# ramanSpectrometer_imagingBoard_CCD.net
KiCad netlist of a schematic drawn in EAGLE
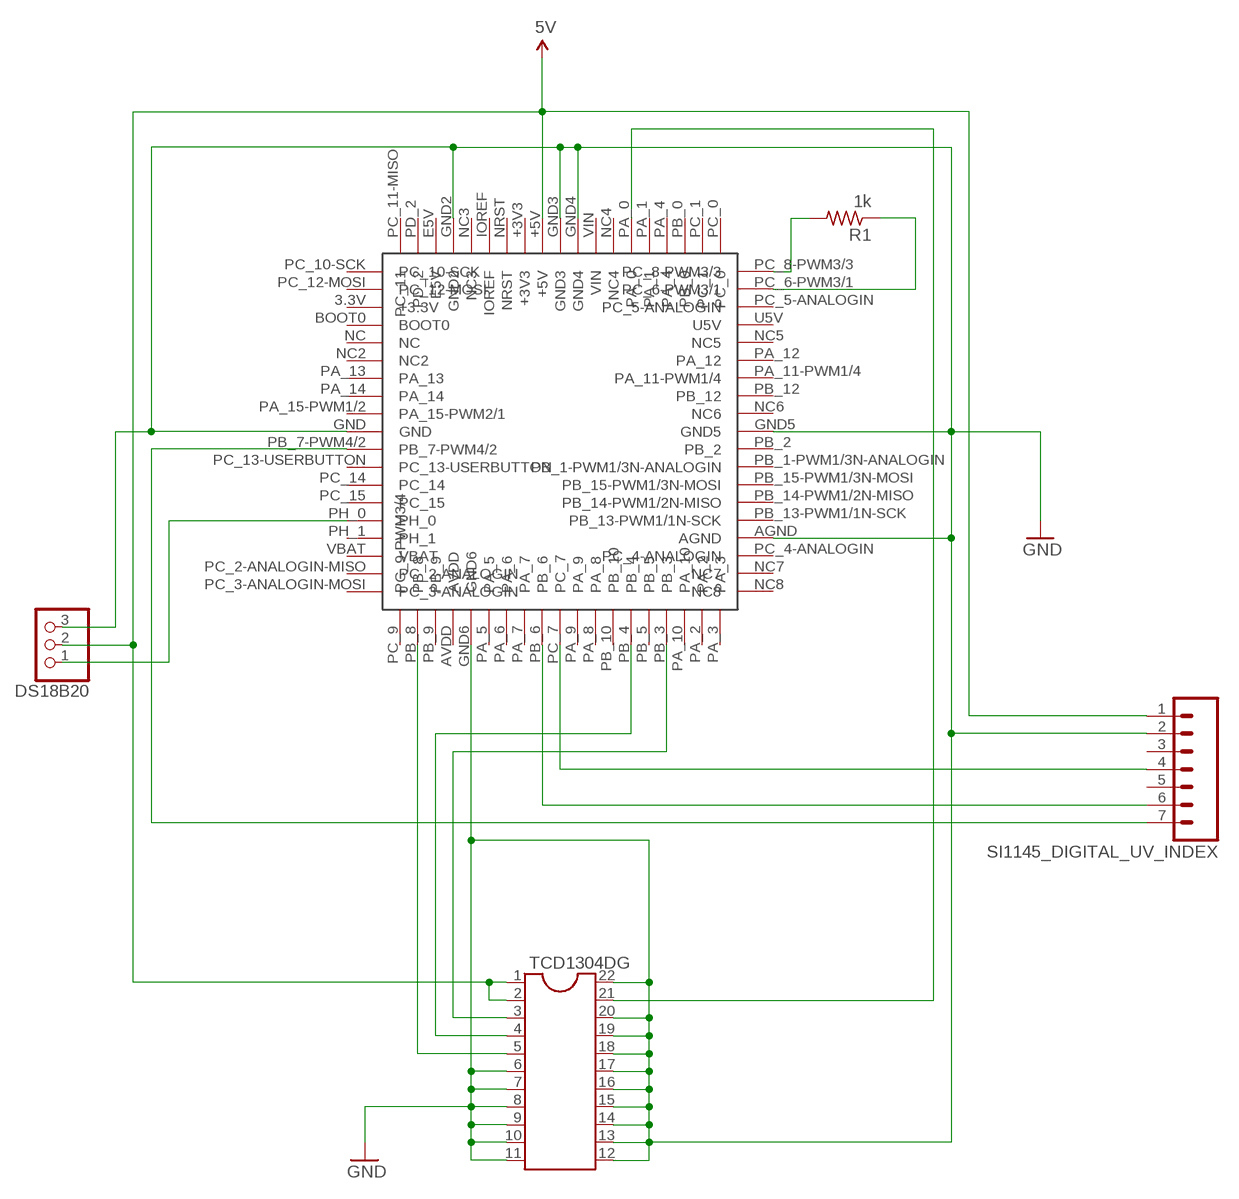
[diagram p0: schematic, sheet 1]

(export (version "E")
  (design (tool "Eeschema 10.0.6"))
  (components
    (comp (ref "DS18B20")
      (value "PINHD-1X3")
      (footprint "eagle-import:1X03")
      (libsource (lib "eagle-import") (part "PINHD-1X3"))
    )
    (comp (ref "R1")
      (value "1k")
      (footprint "eagle-import:M1206")
      (libsource (lib "eagle-import") (part "R-US_M1206"))
    )
    (comp (ref "SI1145_DIGITAL_UV_INDEX")
      (value "M07LOCK")
      (footprint "eagle-import:1X07_LOCK")
      (libsource (lib "eagle-import") (part "M07LOCK"))
    )
    (comp (ref "TCD1304DG")
      (value "DIL22-4")
      (footprint "eagle-import:DIL22-4")
      (libsource (lib "eagle-import") (part "DIL22-4"))
    )
    (comp (ref "U$1")
      (value "STNUCLEOF401RE")
      (footprint "eagle-import:F401-RE")
      (libsource (lib "eagle-import") (part "STNUCLEOF401RE"))
    )
  )
  (nets
    (net (code "1") (name "/+3.3V") (class "Default")
      (node (ref "U$1") (pin "3.3V") (pinfunction "+3.3V_3.3V") (pintype "power_in"))
    )
    (net (code "2") (name "/AVDD") (class "Default")
      (node (ref "U$1") (pin "AVDD") (pinfunction "AVDD_AVDD") (pintype "power_in"))
    )
    (net (code "3") (name "/E5V") (class "Default")
      (node (ref "U$1") (pin "E5V") (pinfunction "E5V_E5V") (pintype "power_in"))
    )
    (net (code "4") (name "/NC6") (class "Default")
      (node (ref "U$1") (pin "NC6") (pinfunction "NC6_NC6") (pintype "power_in"))
    )
    (net (code "5") (name "/VBAT") (class "Default")
      (node (ref "U$1") (pin "VBAT") (pinfunction "VBAT_VBAT") (pintype "power_in"))
    )
    (net (code "6") (name "5V") (class "Default")
      (node (ref "DS18B20") (pin "2") (pinfunction "2_2") (pintype "passive"))
      (node (ref "SI1145_DIGITAL_UV_INDEX") (pin "1") (pinfunction "1_1") (pintype "passive"))
      (node (ref "TCD1304DG") (pin "1") (pinfunction "1_1") (pintype "passive"))
      (node (ref "TCD1304DG") (pin "2") (pinfunction "2_2") (pintype "passive"))
      (node (ref "U$1") (pin "+5V") (pinfunction "+5V_+5V") (pintype "bidirectional"))
    )
    (net (code "7") (name "GND") (class "Default")
      (node (ref "DS18B20") (pin "3") (pinfunction "3_3") (pintype "passive"))
      (node (ref "SI1145_DIGITAL_UV_INDEX") (pin "2") (pinfunction "2_2") (pintype "passive"))
      (node (ref "TCD1304DG") (pin "10") (pinfunction "10_10") (pintype "passive"))
      (node (ref "TCD1304DG") (pin "11") (pinfunction "11_11") (pintype "passive"))
      (node (ref "TCD1304DG") (pin "12") (pinfunction "12_12") (pintype "passive"))
      (node (ref "TCD1304DG") (pin "13") (pinfunction "13_13") (pintype "passive"))
      (node (ref "TCD1304DG") (pin "14") (pinfunction "14_14") (pintype "passive"))
      (node (ref "TCD1304DG") (pin "15") (pinfunction "15_15") (pintype "passive"))
      (node (ref "TCD1304DG") (pin "16") (pinfunction "16_16") (pintype "passive"))
      (node (ref "TCD1304DG") (pin "17") (pinfunction "17_17") (pintype "passive"))
      (node (ref "TCD1304DG") (pin "18") (pinfunction "18_18") (pintype "passive"))
      (node (ref "TCD1304DG") (pin "19") (pinfunction "19_19") (pintype "passive"))
      (node (ref "TCD1304DG") (pin "20") (pinfunction "20_20") (pintype "passive"))
      (node (ref "TCD1304DG") (pin "22") (pinfunction "22_22") (pintype "passive"))
      (node (ref "TCD1304DG") (pin "6") (pinfunction "6_6") (pintype "passive"))
      (node (ref "TCD1304DG") (pin "7") (pinfunction "7_7") (pintype "passive"))
      (node (ref "TCD1304DG") (pin "8") (pinfunction "8_8") (pintype "passive"))
      (node (ref "TCD1304DG") (pin "9") (pinfunction "9_9") (pintype "passive"))
      (node (ref "U$1") (pin "AGND") (pinfunction "AGND_AGND") (pintype "power_in"))
      (node (ref "U$1") (pin "GND") (pinfunction "GND_GND") (pintype "power_in"))
      (node (ref "U$1") (pin "GND2") (pinfunction "GND2_GND2") (pintype "power_in"))
      (node (ref "U$1") (pin "GND3") (pinfunction "GND3_GND3") (pintype "bidirectional"))
      (node (ref "U$1") (pin "GND4") (pinfunction "GND4_GND4") (pintype "bidirectional"))
      (node (ref "U$1") (pin "GND5") (pinfunction "GND5_GND5") (pintype "bidirectional"))
      (node (ref "U$1") (pin "GND6") (pinfunction "GND6_GND6") (pintype "bidirectional"))
    )
    (net (code "8") (name "Net-(DS18B20-Pad1)") (class "Default")
      (node (ref "DS18B20") (pin "1") (pinfunction "1_1") (pintype "passive"))
      (node (ref "U$1") (pin "PH_0") (pinfunction "PH_0_PH_0") (pintype "bidirectional"))
    )
    (net (code "9") (name "Net-(R1-Pad1)") (class "Default")
      (node (ref "R1") (pin "1") (pinfunction "1_1") (pintype "passive"))
      (node (ref "U$1") (pin "PC_6-PWM3/1") (pinfunction "PC_6-PWM3/1_PC_6-PWM3/1") (pintype "bidirectional"))
    )
    (net (code "10") (name "Net-(R1-Pad2)") (class "Default")
      (node (ref "R1") (pin "2") (pinfunction "2_2") (pintype "passive"))
      (node (ref "U$1") (pin "PC_8-PWM3/3") (pinfunction "PC_8-PWM3/3_PC_8-PWM3/3") (pintype "bidirectional"))
    )
    (net (code "11") (name "Net-(SI1145_DIGITAL_UV_INDEX-Pad4)") (class "Default")
      (node (ref "SI1145_DIGITAL_UV_INDEX") (pin "4") (pinfunction "4_4") (pintype "passive"))
      (node (ref "U$1") (pin "PC_7") (pinfunction "PC_7_PC_7") (pintype "bidirectional"))
    )
    (net (code "12") (name "Net-(SI1145_DIGITAL_UV_INDEX-Pad6)") (class "Default")
      (node (ref "SI1145_DIGITAL_UV_INDEX") (pin "6") (pinfunction "6_6") (pintype "passive"))
      (node (ref "U$1") (pin "PB_6") (pinfunction "PB_6_PB_6") (pintype "bidirectional"))
    )
    (net (code "13") (name "Net-(SI1145_DIGITAL_UV_INDEX-Pad7)") (class "Default")
      (node (ref "SI1145_DIGITAL_UV_INDEX") (pin "7") (pinfunction "7_7") (pintype "passive"))
      (node (ref "U$1") (pin "PB_7-PWM4/2") (pinfunction "PB_7-PWM4/2_PB_7-PWM4/2") (pintype "bidirectional"))
    )
    (net (code "14") (name "Net-(TCD1304DG-Pad3)") (class "Default")
      (node (ref "TCD1304DG") (pin "3") (pinfunction "3_3") (pintype "passive"))
      (node (ref "U$1") (pin "PB_3") (pinfunction "PB_3_PB_3") (pintype "bidirectional"))
    )
    (net (code "15") (name "Net-(TCD1304DG-Pad4)") (class "Default")
      (node (ref "TCD1304DG") (pin "4") (pinfunction "4_4") (pintype "passive"))
      (node (ref "U$1") (pin "PB_4") (pinfunction "PB_4_PB_4") (pintype "bidirectional"))
    )
    (net (code "16") (name "Net-(TCD1304DG-Pad5)") (class "Default")
      (node (ref "TCD1304DG") (pin "5") (pinfunction "5_5") (pintype "passive"))
      (node (ref "U$1") (pin "PB_8") (pinfunction "PB_8_PB_8") (pintype "bidirectional"))
    )
    (net (code "17") (name "Net-(TCD1304DG-Pad21)") (class "Default")
      (node (ref "TCD1304DG") (pin "21") (pinfunction "21_21") (pintype "passive"))
      (node (ref "U$1") (pin "PA_0") (pinfunction "PA_0_PA_0") (pintype "bidirectional"))
    )
    (net (code "18") (name "unconnected-(SI1145_DIGITAL_UV_INDEX-Pad3)") (class "Default")
      (node (ref "SI1145_DIGITAL_UV_INDEX") (pin "3") (pinfunction "3_3") (pintype "passive"))
    )
    (net (code "19") (name "unconnected-(SI1145_DIGITAL_UV_INDEX-Pad5)") (class "Default")
      (node (ref "SI1145_DIGITAL_UV_INDEX") (pin "5") (pinfunction "5_5") (pintype "passive"))
    )
    (net (code "20") (name "unconnected-(U$1-PA_15-PWM2{slash}1-PadPA_15-PWM1{slash}2)") (class "Default")
      (node (ref "U$1") (pin "PA_15-PWM1/2") (pinfunction "PA_15-PWM2/1_PA_15-PWM1/2") (pintype "bidirectional"))
    )
    (net (code "21") (name "unconnected-(U$1-PC_2-ANALOGIN-PadPC_2-ANALOGIN-MISO)") (class "Default")
      (node (ref "U$1") (pin "PC_2-ANALOGIN-MISO") (pinfunction "PC_2-ANALOGIN_PC_2-ANALOGIN-MISO") (pintype "bidirectional"))
    )
    (net (code "22") (name "unconnected-(U$1-PC_3-ANALOGIN-PadPC_3-ANALOGIN-MOSI)") (class "Default")
      (node (ref "U$1") (pin "PC_3-ANALOGIN-MOSI") (pinfunction "PC_3-ANALOGIN_PC_3-ANALOGIN-MOSI") (pintype "bidirectional"))
    )
    (net (code "23") (name "unconnected-(U$1-PC_9-PWM3{slash}4-PadPC_9)") (class "Default")
      (node (ref "U$1") (pin "PC_9") (pinfunction "PC_9-PWM3/4_PC_9") (pintype "bidirectional"))
    )
    (net (code "24") (name "unconnected-(U$1-PC_11-PadPC_11-MISO)") (class "Default")
      (node (ref "U$1") (pin "PC_11-MISO") (pinfunction "PC_11_PC_11-MISO") (pintype "bidirectional"))
    )
    (net (code "25") (name "unconnected-(U$1-Pad+3V3)") (class "Default")
      (node (ref "U$1") (pin "+3V3") (pinfunction "+3V3_+3V3") (pintype "bidirectional"))
    )
    (net (code "26") (name "unconnected-(U$1-PadBOOT0)") (class "Default")
      (node (ref "U$1") (pin "BOOT0") (pinfunction "BOOT0_BOOT0") (pintype "bidirectional"))
    )
    (net (code "27") (name "unconnected-(U$1-PadIOREF)") (class "Default")
      (node (ref "U$1") (pin "IOREF") (pinfunction "IOREF_IOREF") (pintype "bidirectional"))
    )
    (net (code "28") (name "unconnected-(U$1-PadNC)") (class "Default")
      (node (ref "U$1") (pin "NC") (pinfunction "NC_NC") (pintype "no_connect"))
    )
    (net (code "29") (name "unconnected-(U$1-PadNC2)") (class "Default")
      (node (ref "U$1") (pin "NC2") (pinfunction "NC2_NC2") (pintype "no_connect"))
    )
    (net (code "30") (name "unconnected-(U$1-PadNC3)") (class "Default")
      (node (ref "U$1") (pin "NC3") (pinfunction "NC3_NC3") (pintype "no_connect"))
    )
    (net (code "31") (name "unconnected-(U$1-PadNC4)") (class "Default")
      (node (ref "U$1") (pin "NC4") (pinfunction "NC4_NC4") (pintype "bidirectional"))
    )
    (net (code "32") (name "unconnected-(U$1-PadNC5)") (class "Default")
      (node (ref "U$1") (pin "NC5") (pinfunction "NC5_NC5") (pintype "bidirectional"))
    )
    (net (code "33") (name "unconnected-(U$1-PadNC7)") (class "Default")
      (node (ref "U$1") (pin "NC7") (pinfunction "NC7_NC7") (pintype "bidirectional"))
    )
    (net (code "34") (name "unconnected-(U$1-PadNC8)") (class "Default")
      (node (ref "U$1") (pin "NC8") (pinfunction "NC8_NC8") (pintype "bidirectional"))
    )
    (net (code "35") (name "unconnected-(U$1-PadNRST)") (class "Default")
      (node (ref "U$1") (pin "NRST") (pinfunction "NRST_NRST") (pintype "bidirectional"))
    )
    (net (code "36") (name "unconnected-(U$1-PadPA_1)") (class "Default")
      (node (ref "U$1") (pin "PA_1") (pinfunction "PA_1_PA_1") (pintype "bidirectional"))
    )
    (net (code "37") (name "unconnected-(U$1-PadPA_2)") (class "Default")
      (node (ref "U$1") (pin "PA_2") (pinfunction "PA_2_PA_2") (pintype "bidirectional"))
    )
    (net (code "38") (name "unconnected-(U$1-PadPA_3)") (class "Default")
      (node (ref "U$1") (pin "PA_3") (pinfunction "PA_3_PA_3") (pintype "bidirectional"))
    )
    (net (code "39") (name "unconnected-(U$1-PadPA_4)") (class "Default")
      (node (ref "U$1") (pin "PA_4") (pinfunction "PA_4_PA_4") (pintype "bidirectional"))
    )
    (net (code "40") (name "unconnected-(U$1-PadPA_5)") (class "Default")
      (node (ref "U$1") (pin "PA_5") (pinfunction "PA_5_PA_5") (pintype "bidirectional"))
    )
    (net (code "41") (name "unconnected-(U$1-PadPA_6)") (class "Default")
      (node (ref "U$1") (pin "PA_6") (pinfunction "PA_6_PA_6") (pintype "bidirectional"))
    )
    (net (code "42") (name "unconnected-(U$1-PadPA_7)") (class "Default")
      (node (ref "U$1") (pin "PA_7") (pinfunction "PA_7_PA_7") (pintype "bidirectional"))
    )
    (net (code "43") (name "unconnected-(U$1-PadPA_8)") (class "Default")
      (node (ref "U$1") (pin "PA_8") (pinfunction "PA_8_PA_8") (pintype "bidirectional"))
    )
    (net (code "44") (name "unconnected-(U$1-PadPA_9)") (class "Default")
      (node (ref "U$1") (pin "PA_9") (pinfunction "PA_9_PA_9") (pintype "bidirectional"))
    )
    (net (code "45") (name "unconnected-(U$1-PadPA_10)") (class "Default")
      (node (ref "U$1") (pin "PA_10") (pinfunction "PA_10_PA_10") (pintype "bidirectional"))
    )
    (net (code "46") (name "unconnected-(U$1-PadPA_11-PWM1{slash}4)") (class "Default")
      (node (ref "U$1") (pin "PA_11-PWM1/4") (pinfunction "PA_11-PWM1/4_PA_11-PWM1/4") (pintype "bidirectional"))
    )
    (net (code "47") (name "unconnected-(U$1-PadPA_12)") (class "Default")
      (node (ref "U$1") (pin "PA_12") (pinfunction "PA_12_PA_12") (pintype "bidirectional"))
    )
    (net (code "48") (name "unconnected-(U$1-PadPA_13)") (class "Default")
      (node (ref "U$1") (pin "PA_13") (pinfunction "PA_13_PA_13") (pintype "bidirectional"))
    )
    (net (code "49") (name "unconnected-(U$1-PadPA_14)") (class "Default")
      (node (ref "U$1") (pin "PA_14") (pinfunction "PA_14_PA_14") (pintype "bidirectional"))
    )
    (net (code "50") (name "unconnected-(U$1-PadPB_0)") (class "Default")
      (node (ref "U$1") (pin "PB_0") (pinfunction "PB_0_PB_0") (pintype "bidirectional"))
    )
    (net (code "51") (name "unconnected-(U$1-PadPB_1-PWM1{slash}3N-ANALOGIN)") (class "Default")
      (node (ref "U$1") (pin "PB_1-PWM1/3N-ANALOGIN") (pinfunction "PB_1-PWM1/3N-ANALOGIN_PB_1-PWM1/3N-ANALOGIN") (pintype "bidirectional"))
    )
    (net (code "52") (name "unconnected-(U$1-PadPB_2)") (class "Default")
      (node (ref "U$1") (pin "PB_2") (pinfunction "PB_2_PB_2") (pintype "bidirectional"))
    )
    (net (code "53") (name "unconnected-(U$1-PadPB_5)") (class "Default")
      (node (ref "U$1") (pin "PB_5") (pinfunction "PB_5_PB_5") (pintype "bidirectional"))
    )
    (net (code "54") (name "unconnected-(U$1-PadPB_9)") (class "Default")
      (node (ref "U$1") (pin "PB_9") (pinfunction "PB_9_PB_9") (pintype "bidirectional"))
    )
    (net (code "55") (name "unconnected-(U$1-PadPB_10)") (class "Default")
      (node (ref "U$1") (pin "PB_10") (pinfunction "PB_10_PB_10") (pintype "bidirectional"))
    )
    (net (code "56") (name "unconnected-(U$1-PadPB_12)") (class "Default")
      (node (ref "U$1") (pin "PB_12") (pinfunction "PB_12_PB_12") (pintype "bidirectional"))
    )
    (net (code "57") (name "unconnected-(U$1-PadPB_13-PWM1{slash}1N-SCK)") (class "Default")
      (node (ref "U$1") (pin "PB_13-PWM1/1N-SCK") (pinfunction "PB_13-PWM1/1N-SCK_PB_13-PWM1/1N-SCK") (pintype "bidirectional"))
    )
    (net (code "58") (name "unconnected-(U$1-PadPB_14-PWM1{slash}2N-MISO)") (class "Default")
      (node (ref "U$1") (pin "PB_14-PWM1/2N-MISO") (pinfunction "PB_14-PWM1/2N-MISO_PB_14-PWM1/2N-MISO") (pintype "bidirectional"))
    )
    (net (code "59") (name "unconnected-(U$1-PadPB_15-PWM1{slash}3N-MOSI)") (class "Default")
      (node (ref "U$1") (pin "PB_15-PWM1/3N-MOSI") (pinfunction "PB_15-PWM1/3N-MOSI_PB_15-PWM1/3N-MOSI") (pintype "bidirectional"))
    )
    (net (code "60") (name "unconnected-(U$1-PadPC_0)") (class "Default")
      (node (ref "U$1") (pin "PC_0") (pinfunction "PC_0_PC_0") (pintype "bidirectional"))
    )
    (net (code "61") (name "unconnected-(U$1-PadPC_1)") (class "Default")
      (node (ref "U$1") (pin "PC_1") (pinfunction "PC_1_PC_1") (pintype "bidirectional"))
    )
    (net (code "62") (name "unconnected-(U$1-PadPC_4-ANALOGIN)") (class "Default")
      (node (ref "U$1") (pin "PC_4-ANALOGIN") (pinfunction "PC_4-ANALOGIN_PC_4-ANALOGIN") (pintype "bidirectional"))
    )
    (net (code "63") (name "unconnected-(U$1-PadPC_5-ANALOGIN)") (class "Default")
      (node (ref "U$1") (pin "PC_5-ANALOGIN") (pinfunction "PC_5-ANALOGIN_PC_5-ANALOGIN") (pintype "bidirectional"))
    )
    (net (code "64") (name "unconnected-(U$1-PadPC_10-SCK)") (class "Default")
      (node (ref "U$1") (pin "PC_10-SCK") (pinfunction "PC_10-SCK_PC_10-SCK") (pintype "bidirectional"))
    )
    (net (code "65") (name "unconnected-(U$1-PadPC_12-MOSI)") (class "Default")
      (node (ref "U$1") (pin "PC_12-MOSI") (pinfunction "PC_12-MOSI_PC_12-MOSI") (pintype "bidirectional"))
    )
    (net (code "66") (name "unconnected-(U$1-PadPC_13-USERBUTTON)") (class "Default")
      (node (ref "U$1") (pin "PC_13-USERBUTTON") (pinfunction "PC_13-USERBUTTON_PC_13-USERBUTTON") (pintype "bidirectional"))
    )
    (net (code "67") (name "unconnected-(U$1-PadPC_14)") (class "Default")
      (node (ref "U$1") (pin "PC_14") (pinfunction "PC_14_PC_14") (pintype "bidirectional"))
    )
    (net (code "68") (name "unconnected-(U$1-PadPC_15)") (class "Default")
      (node (ref "U$1") (pin "PC_15") (pinfunction "PC_15_PC_15") (pintype "bidirectional"))
    )
    (net (code "69") (name "unconnected-(U$1-PadPD_2)") (class "Default")
      (node (ref "U$1") (pin "PD_2") (pinfunction "PD_2_PD_2") (pintype "bidirectional"))
    )
    (net (code "70") (name "unconnected-(U$1-PadPH_1)") (class "Default")
      (node (ref "U$1") (pin "PH_1") (pinfunction "PH_1_PH_1") (pintype "bidirectional"))
    )
    (net (code "71") (name "unconnected-(U$1-PadU5V)") (class "Default")
      (node (ref "U$1") (pin "U5V") (pinfunction "U5V_U5V") (pintype "bidirectional"))
    )
    (net (code "72") (name "unconnected-(U$1-PadVIN)") (class "Default")
      (node (ref "U$1") (pin "VIN") (pinfunction "VIN_VIN") (pintype "bidirectional"))
    )
  )
)
